# Sheet1.net
KiCad netlist of a schematic drawn in Altium Designer
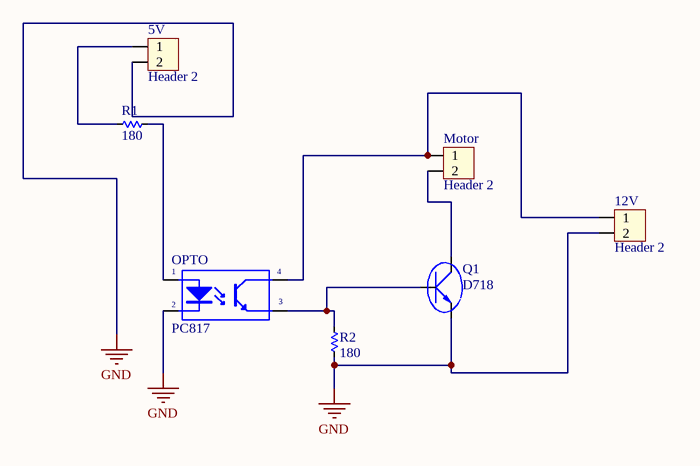
[diagram p0: Sheet1.SchDoc]

(export (version "E")
  (design (tool "Eeschema 10.0.6"))
  (components
    (comp (ref "5V")
      (value "Header 2")
      (footprint "HED2")
      (description "Header 2 (Green)")
      (libsource (lib "syhaunguyen__1") (part "Hed2"))
    )
    (comp (ref "12V")
      (value "Header 2")
      (footprint "HED2")
      (description "Header 2 (Green)")
      (libsource (lib "syhaunguyen__1") (part "Hed2"))
    )
    (comp (ref "Motor")
      (value "Header 2")
      (footprint "HED2")
      (description "Header 2 (Green)")
      (libsource (lib "syhaunguyen__1") (part "Hed2"))
    )
    (comp (ref "OPTO")
      (value "PC817")
      (footprint "DIP4")
      (description "Single Opto")
      (libsource (lib "Library1") (part "PC817"))
    )
    (comp (ref "Q1")
      (value "D718")
      (footprint "QTO-247")
      (description "Transistor Power Supply")
      (libsource (lib "minhha") (part "D718"))
    )
    (comp (ref "R1")
      (value "180")
      (footprint "RES-1/2W")
      (description "Res")
      (fields
        (field (name "MANUFACTURER") "Generic Components")
        (field (name "PUBLISHER") "Altium Hobart Technology Centre")
      )
      (libsource (lib "Library1") (part "Res"))
    )
    (comp (ref "R2")
      (value "180")
      (footprint "RES-1/2W")
      (description "Res")
      (fields
        (field (name "MANUFACTURER") "Generic Components")
        (field (name "PUBLISHER") "Altium Hobart Technology Centre")
      )
      (libsource (lib "Library1") (part "Res"))
    )
  )
  (nets
    (net (code "1") (name "GND") (class "Default")
      (node (ref "12V") (pin "2") (pinfunction "2_2") (pintype "passive"))
      (node (ref "5V") (pin "2") (pinfunction "2_2") (pintype "passive"))
      (node (ref "OPTO") (pin "2") (pinfunction "K_2") (pintype "passive"))
      (node (ref "Q1") (pin "3") (pinfunction "E_3") (pintype "passive"))
      (node (ref "R2") (pin "2") (pinfunction "2_2") (pintype "passive"))
    )
    (net (code "2") (name "Net-(5V-Pad1)") (class "Default")
      (node (ref "5V") (pin "1") (pinfunction "1_1") (pintype "passive"))
      (node (ref "R1") (pin "1") (pinfunction "1_1") (pintype "passive"))
    )
    (net (code "3") (name "Net-(OPTO-A)") (class "Default")
      (node (ref "OPTO") (pin "1") (pinfunction "A_1") (pintype "passive"))
      (node (ref "R1") (pin "2") (pinfunction "2_2") (pintype "passive"))
    )
    (net (code "4") (name "Net-(OPTO-C)") (class "Default")
      (node (ref "12V") (pin "1") (pinfunction "1_1") (pintype "passive"))
      (node (ref "Motor") (pin "1") (pinfunction "1_1") (pintype "passive"))
      (node (ref "OPTO") (pin "4") (pinfunction "C_4") (pintype "passive"))
    )
    (net (code "5") (name "Net-(OPTO-E)") (class "Default")
      (node (ref "OPTO") (pin "3") (pinfunction "E_3") (pintype "passive"))
      (node (ref "Q1") (pin "1") (pinfunction "B_1") (pintype "passive"))
      (node (ref "R2") (pin "1") (pinfunction "1_1") (pintype "passive"))
    )
    (net (code "6") (name "Net-(Q1-C)") (class "Default")
      (node (ref "Motor") (pin "2") (pinfunction "2_2") (pintype "passive"))
      (node (ref "Q1") (pin "2") (pinfunction "C_2") (pintype "passive"))
    )
  )
)
